# KelvinVoltageMeasureModule.net
KiCad netlist of a schematic drawn in Altium Designer
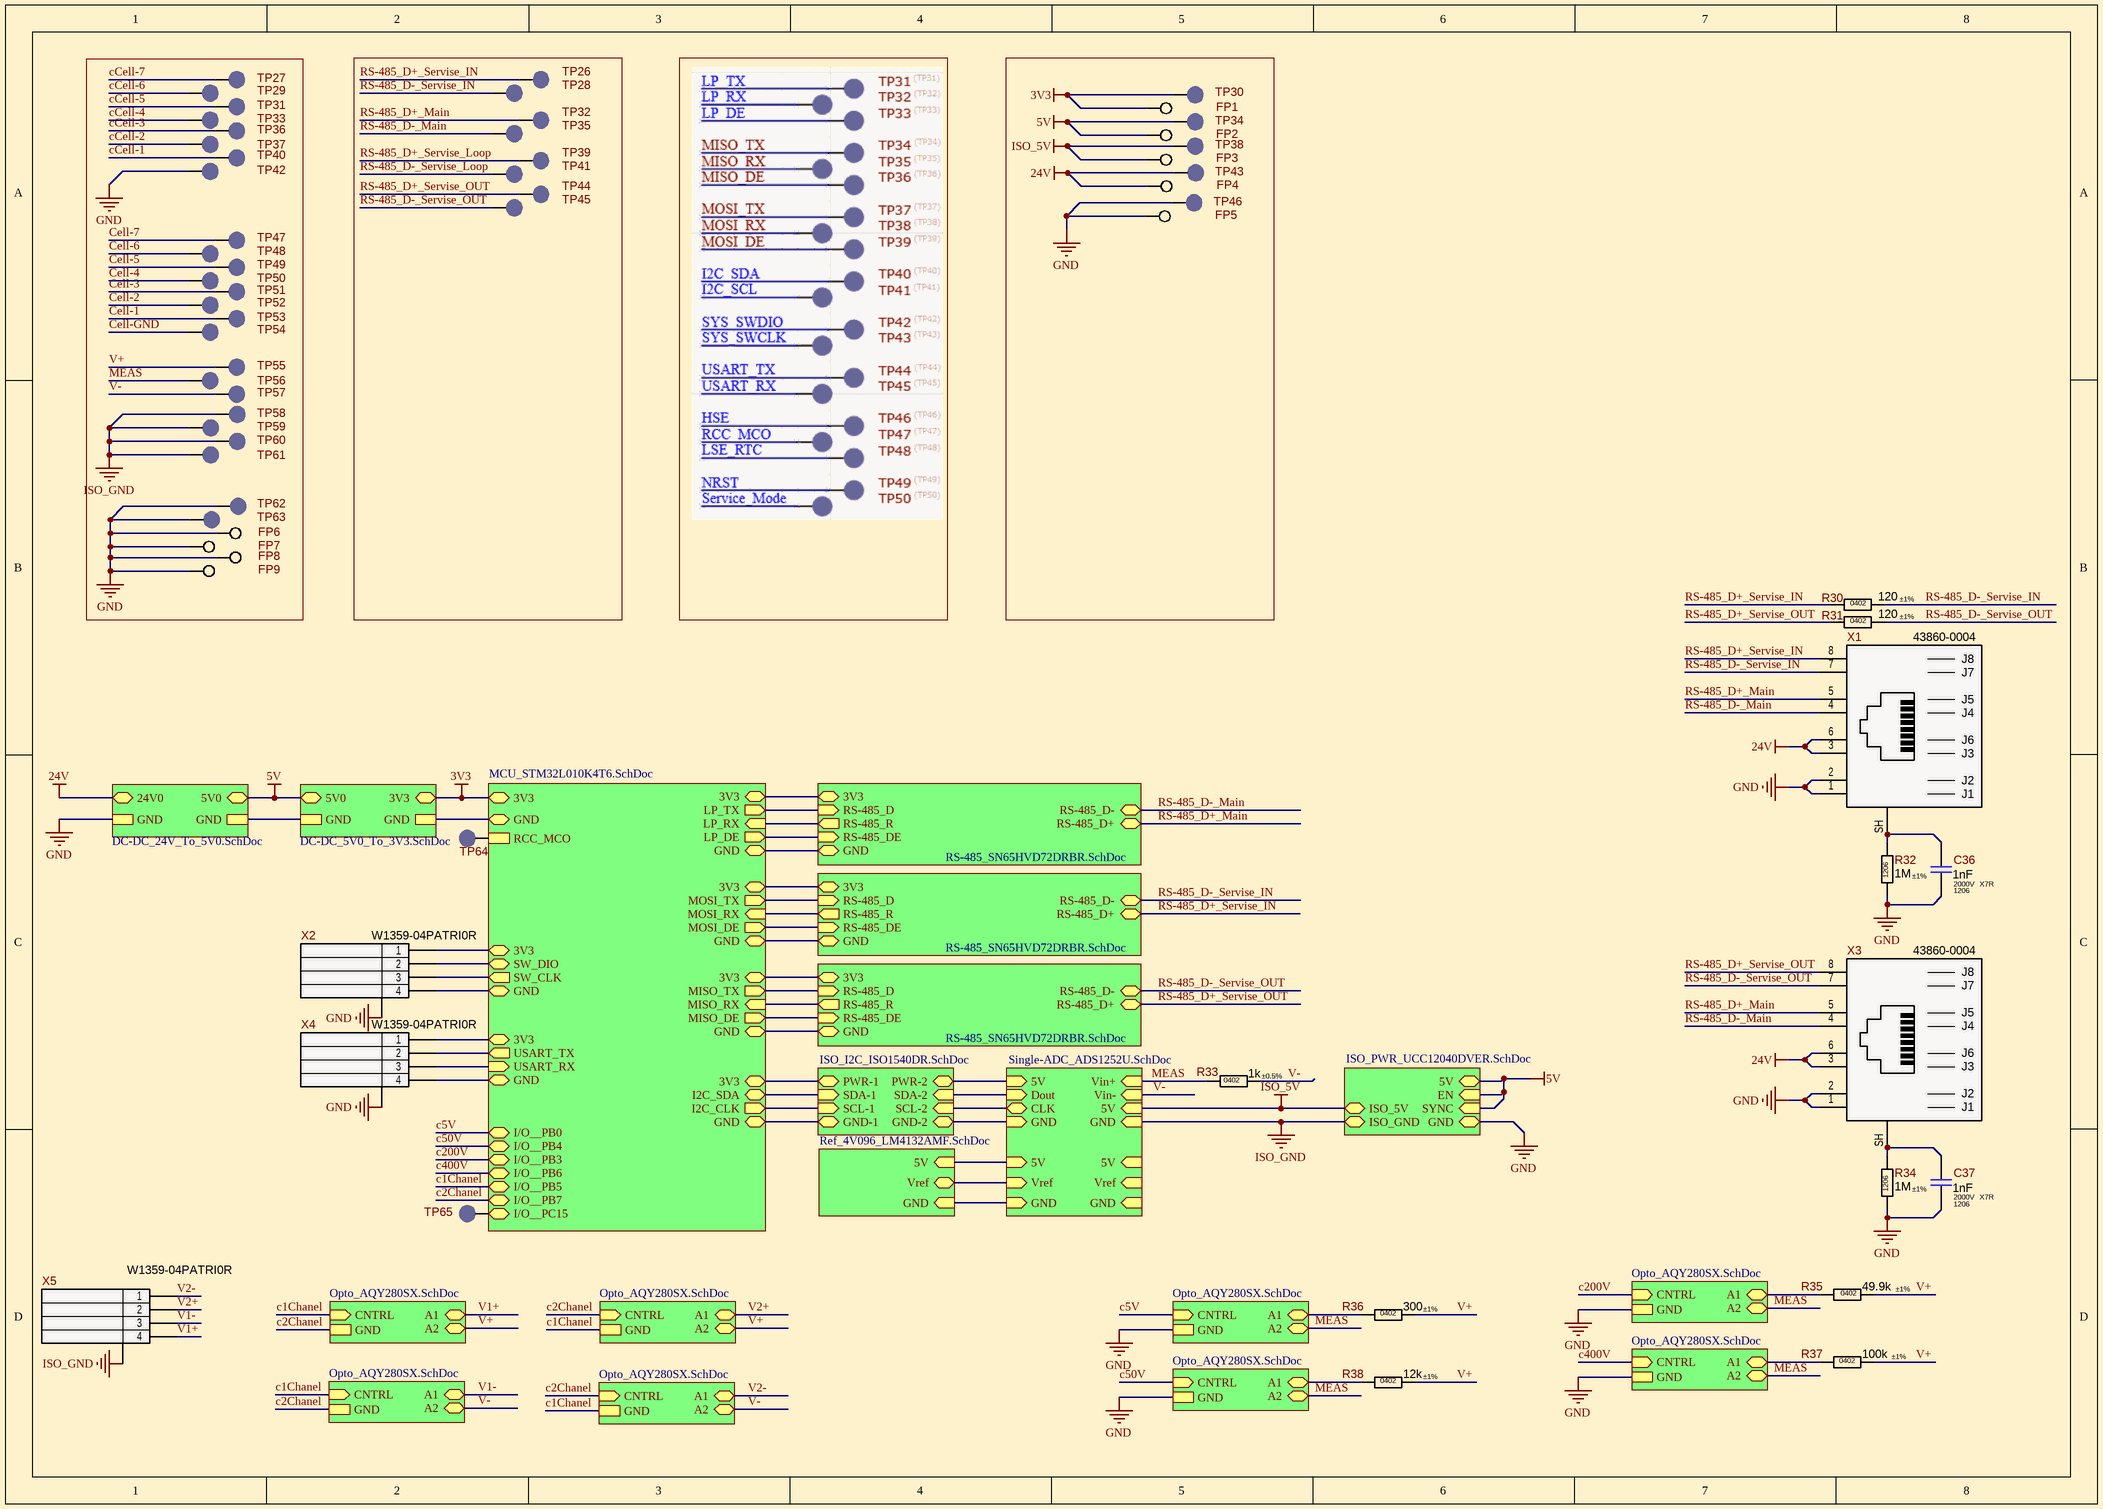
[diagram p0: KelvinVoltageMeasureModule.SchDoc]

(export (version "E")
  (design (tool "Eeschema 10.0.6"))
  (components
    (comp (ref "C36")
      (value "1nF")
      (footprint "CAP-1206(3216)X125T20")
      (description "1nF 2000V X7R ±10% 1206 Ceramic Capacitor RoHS")
      (fields
        (field (name "PACKAGE") "1206")
        (field (name "VOLTAGE") "2000V")
        (field (name "DIELECTRIC TYPE") "X7R")
        (field (name "PART NUMBER") "CC1206KKX7RDBB102")
        (field (name "MANUFACTURER") "Yageo")
      )
      (libsource (lib "EL.CVCM.T01") (part "Capacitor-NonPolar"))
    )
    (comp (ref "C37")
      (value "1nF")
      (footprint "CAP-1206(3216)X125T20")
      (description "1nF 2000V X7R ±10% 1206 Ceramic Capacitor RoHS")
      (fields
        (field (name "PACKAGE") "1206")
        (field (name "VOLTAGE") "2000V")
        (field (name "DIELECTRIC TYPE") "X7R")
        (field (name "PART NUMBER") "CC1206KKX7RDBB102")
        (field (name "MANUFACTURER") "Yageo")
      )
      (libsource (lib "EL.CVCM.T01") (part "Capacitor-NonPolar"))
    )
    (comp (ref "FP1")
      (value "PAD-1.1mm")
      (footprint "PAD-1.1mm")
      (description "1.1mm Pad for Plug-In or Receptacle")
      (fields (field (name "MANUFACTURER") "NONE"))
      (libsource (lib "EL.CVCM.T01") (part "Pad"))
    )
    (comp (ref "FP2")
      (value "PAD-1.1mm")
      (footprint "PAD-1.1mm")
      (description "1.1mm Pad for Plug-In or Receptacle")
      (fields (field (name "MANUFACTURER") "NONE"))
      (libsource (lib "EL.CVCM.T01") (part "Pad"))
    )
    (comp (ref "FP3")
      (value "PAD-1.1mm")
      (footprint "PAD-1.1mm")
      (description "1.1mm Pad for Plug-In or Receptacle")
      (fields (field (name "MANUFACTURER") "NONE"))
      (libsource (lib "EL.CVCM.T01") (part "Pad"))
    )
    (comp (ref "FP4")
      (value "PAD-1.1mm")
      (footprint "PAD-1.1mm")
      (description "1.1mm Pad for Plug-In or Receptacle")
      (fields (field (name "MANUFACTURER") "NONE"))
      (libsource (lib "EL.CVCM.T01") (part "Pad"))
    )
    (comp (ref "FP5")
      (value "PAD-1.1mm")
      (footprint "PAD-1.1mm")
      (description "1.1mm Pad for Plug-In or Receptacle")
      (fields (field (name "MANUFACTURER") "NONE"))
      (libsource (lib "EL.CVCM.T01") (part "Pad"))
    )
    (comp (ref "FP6")
      (value "PAD-1.1mm")
      (footprint "PAD-1.1mm")
      (description "1.1mm Pad for Plug-In or Receptacle")
      (fields (field (name "MANUFACTURER") "NONE"))
      (libsource (lib "EL.CVCM.T01") (part "Pad"))
    )
    (comp (ref "FP7")
      (value "PAD-1.1mm")
      (footprint "PAD-1.1mm")
      (description "1.1mm Pad for Plug-In or Receptacle")
      (fields (field (name "MANUFACTURER") "NONE"))
      (libsource (lib "EL.CVCM.T01") (part "Pad"))
    )
    (comp (ref "FP8")
      (value "PAD-1.1mm")
      (footprint "PAD-1.1mm")
      (description "1.1mm Pad for Plug-In or Receptacle")
      (fields (field (name "MANUFACTURER") "NONE"))
      (libsource (lib "EL.CVCM.T01") (part "Pad"))
    )
    (comp (ref "FP9")
      (value "PAD-1.1mm")
      (footprint "PAD-1.1mm")
      (description "1.1mm Pad for Plug-In or Receptacle")
      (fields (field (name "MANUFACTURER") "NONE"))
      (libsource (lib "EL.CVCM.T01") (part "Pad"))
    )
    (comp (ref "R30")
      (value "120")
      (footprint "R_ANY_CHIP_0402_HI")
      (description "120 Ohms ±1% 1/16W 0402 Thick Film Resistor")
      (fields
        (field (name "TOLERANCE") "±1%")
        (field (name "PACKAGE") "0402")
        (field (name "PART NUMBER") "RC0402FR-07120RL")
        (field (name "MANUFACTURER") "Yageo")
      )
      (libsource (lib "EL.CVCM.T01") (part "Resistor"))
    )
    (comp (ref "R31")
      (value "120")
      (footprint "R_ANY_CHIP_0402_HI")
      (description "120 Ohms ±1% 1/16W 0402 Thick Film Resistor")
      (fields
        (field (name "TOLERANCE") "±1%")
        (field (name "PACKAGE") "0402")
        (field (name "PART NUMBER") "RC0402FR-07120RL")
        (field (name "MANUFACTURER") "Yageo")
      )
      (libsource (lib "EL.CVCM.T01") (part "Resistor"))
    )
    (comp (ref "R32")
      (value "1M")
      (footprint "CHV1206-Series")
      (description "1 MOhms ±1%, 1/4W 1206 Thick Film Resistor")
      (fields
        (field (name "TOLERANCE") "±1%")
        (field (name "PACKAGE") "1206")
        (field (name "PART NUMBER") "CHV1206-FX-1004ELF")
        (field (name "MANUFACTURER") "Bourns")
      )
      (libsource (lib "EL.CVCM.T01") (part "Resistor"))
    )
    (comp (ref "R33")
      (value "1k")
      (footprint "R_ANY_CHIP_0402_MED")
      (description "1 kOhms ±0.5% 1/16W 0402 Thick Film Resistor")
      (fields
        (field (name "TOLERANCE") "±0.5%")
        (field (name "PACKAGE") "0402")
        (field (name "PART NUMBER") "RC0402DR-071KL")
        (field (name "MANUFACTURER") "Yageo")
      )
      (libsource (lib "EL.CVCM.T01") (part "Resistor"))
    )
    (comp (ref "R34")
      (value "1M")
      (footprint "CHV1206-Series")
      (description "1 MOhms ±1%, 1/4W 1206 Thick Film Resistor")
      (fields
        (field (name "TOLERANCE") "±1%")
        (field (name "PACKAGE") "1206")
        (field (name "PART NUMBER") "CHV1206-FX-1004ELF")
        (field (name "MANUFACTURER") "Bourns")
      )
      (libsource (lib "EL.CVCM.T01") (part "Resistor"))
    )
    (comp (ref "R35")
      (value "49.9k")
      (footprint "R_ANY_CHIP_0402_MED")
      (description "49.9 kOhms ±1% 1/16W 0402 Thick Film Resistor")
      (fields
        (field (name "PART NUMBER") "RC0402FR-0749K9L")
        (field (name "MANUFACTURER") "Yageo")
        (field (name "TOLERANCE") "±1%")
        (field (name "PACKAGE") "0402")
      )
      (libsource (lib "EL.XXX.T01") (part "RC0402FR-0749K9L"))
    )
    (comp (ref "R36")
      (value "300")
      (footprint "R_ANY_CHIP_0402_MED")
      (description "300 Ohms ±1% 1/16W 0402 Thick Film Resistor")
      (fields
        (field (name "PART NUMBER") "RC0402FR-07300RL")
        (field (name "MANUFACTURER") "Yageo")
        (field (name "TOLERANCE") "±1%")
        (field (name "PACKAGE") "0402")
      )
      (libsource (lib "EL.XXX.T01") (part "RC0402FR-07300RL"))
    )
    (comp (ref "R37")
      (value "100k")
      (footprint "R_ANY_CHIP_0402_MED")
      (description "100 kOhms ±1% 1/16W 0402 Thick Film Resistor")
      (fields
        (field (name "PART NUMBER") "RC0402FR-07100KL")
        (field (name "MANUFACTURER") "Yageo")
        (field (name "TOLERANCE") "±1%")
        (field (name "PACKAGE") "0402")
      )
      (libsource (lib "EL.XXX.T01") (part "RC0402FR-07100KL"))
    )
    (comp (ref "R38")
      (value "12k")
      (footprint "R_ANY_CHIP_0402_MED")
      (description "12 kOhms ±1% 1/16W 0402 Thick Film Resistor")
      (fields
        (field (name "PART NUMBER") "RC0402FR-0712KL")
        (field (name "MANUFACTURER") "Yageo")
        (field (name "TOLERANCE") "±1%")
        (field (name "PACKAGE") "0402")
      )
      (libsource (lib "EL.XXX.T01") (part "RC0402FR-0712KL"))
    )
    (comp (ref "TP26")
      (value "LED_LINK")
      (footprint "TP_SMD_2mm")
      (description "Test Point SMD Pad 1.0mm/1.5mm/2mm")
      (fields (field (name "PART NUMBER") "TP-PAD-SMD"))
      (libsource (lib "EL.CVCM.T01") (part "Test-Point-SMD-1"))
    )
    (comp (ref "TP27")
      (value "LED_LINK")
      (footprint "TP_SMD_2mm")
      (description "Test Point SMD Pad 1.0mm/1.5mm/2mm")
      (fields (field (name "PART NUMBER") "TP-PAD-SMD"))
      (libsource (lib "EL.CVCM.T01") (part "Test-Point-SMD-1"))
    )
    (comp (ref "TP28")
      (value "LED_LINK")
      (footprint "TP_SMD_2mm")
      (description "Test Point SMD Pad 1.0mm/1.5mm/2mm")
      (fields (field (name "PART NUMBER") "TP-PAD-SMD"))
      (libsource (lib "EL.CVCM.T01") (part "Test-Point-SMD-1"))
    )
    (comp (ref "TP29")
      (value "LED_LINK")
      (footprint "TP_SMD_2mm")
      (description "Test Point SMD Pad 1.0mm/1.5mm/2mm")
      (fields (field (name "PART NUMBER") "TP-PAD-SMD"))
      (libsource (lib "EL.CVCM.T01") (part "Test-Point-SMD-1"))
    )
    (comp (ref "TP30")
      (value "LED_LINK")
      (footprint "TP_SMD_2mm")
      (description "Test Point SMD Pad 1.0mm/1.5mm/2mm")
      (fields (field (name "PART NUMBER") "TP-PAD-SMD"))
      (libsource (lib "EL.CVCM.T01") (part "Test-Point-SMD-1"))
    )
    (comp (ref "TP31")
      (value "LED_LINK")
      (footprint "TP_SMD_2mm")
      (description "Test Point SMD Pad 1.0mm/1.5mm/2mm")
      (fields (field (name "PART NUMBER") "TP-PAD-SMD"))
      (libsource (lib "EL.CVCM.T01") (part "Test-Point-SMD-1"))
    )
    (comp (ref "TP32")
      (value "LED_LINK")
      (footprint "TP_SMD_2mm")
      (description "Test Point SMD Pad 1.0mm/1.5mm/2mm")
      (fields (field (name "PART NUMBER") "TP-PAD-SMD"))
      (libsource (lib "EL.CVCM.T01") (part "Test-Point-SMD-1"))
    )
    (comp (ref "TP33")
      (value "LED_LINK")
      (footprint "TP_SMD_2mm")
      (description "Test Point SMD Pad 1.0mm/1.5mm/2mm")
      (fields (field (name "PART NUMBER") "TP-PAD-SMD"))
      (libsource (lib "EL.CVCM.T01") (part "Test-Point-SMD-1"))
    )
    (comp (ref "TP34")
      (value "LED_LINK")
      (footprint "TP_SMD_2mm")
      (description "Test Point SMD Pad 1.0mm/1.5mm/2mm")
      (fields (field (name "PART NUMBER") "TP-PAD-SMD"))
      (libsource (lib "EL.CVCM.T01") (part "Test-Point-SMD-1"))
    )
    (comp (ref "TP35")
      (value "LED_LINK")
      (footprint "TP_SMD_2mm")
      (description "Test Point SMD Pad 1.0mm/1.5mm/2mm")
      (fields (field (name "PART NUMBER") "TP-PAD-SMD"))
      (libsource (lib "EL.CVCM.T01") (part "Test-Point-SMD-1"))
    )
    (comp (ref "TP36")
      (value "LED_LINK")
      (footprint "TP_SMD_2mm")
      (description "Test Point SMD Pad 1.0mm/1.5mm/2mm")
      (fields (field (name "PART NUMBER") "TP-PAD-SMD"))
      (libsource (lib "EL.CVCM.T01") (part "Test-Point-SMD-1"))
    )
    (comp (ref "TP37")
      (value "LED_LINK")
      (footprint "TP_SMD_2mm")
      (description "Test Point SMD Pad 1.0mm/1.5mm/2mm")
      (fields (field (name "PART NUMBER") "TP-PAD-SMD"))
      (libsource (lib "EL.CVCM.T01") (part "Test-Point-SMD-1"))
    )
    (comp (ref "TP38")
      (value "LED_LINK")
      (footprint "TP_SMD_2mm")
      (description "Test Point SMD Pad 1.0mm/1.5mm/2mm")
      (fields (field (name "PART NUMBER") "TP-PAD-SMD"))
      (libsource (lib "EL.CVCM.T01") (part "Test-Point-SMD-1"))
    )
    (comp (ref "TP39")
      (value "LED_LINK")
      (footprint "TP_SMD_2mm")
      (description "Test Point SMD Pad 1.0mm/1.5mm/2mm")
      (fields (field (name "PART NUMBER") "TP-PAD-SMD"))
      (libsource (lib "EL.CVCM.T01") (part "Test-Point-SMD-1"))
    )
    (comp (ref "TP40")
      (value "LED_LINK")
      (footprint "TP_SMD_2mm")
      (description "Test Point SMD Pad 1.0mm/1.5mm/2mm")
      (fields (field (name "PART NUMBER") "TP-PAD-SMD"))
      (libsource (lib "EL.CVCM.T01") (part "Test-Point-SMD-1"))
    )
    (comp (ref "TP41")
      (value "LED_LINK")
      (footprint "TP_SMD_2mm")
      (description "Test Point SMD Pad 1.0mm/1.5mm/2mm")
      (fields (field (name "PART NUMBER") "TP-PAD-SMD"))
      (libsource (lib "EL.CVCM.T01") (part "Test-Point-SMD-1"))
    )
    (comp (ref "TP42")
      (value "LED_LINK")
      (footprint "TP_SMD_2mm")
      (description "Test Point SMD Pad 1.0mm/1.5mm/2mm")
      (fields (field (name "PART NUMBER") "TP-PAD-SMD"))
      (libsource (lib "EL.CVCM.T01") (part "Test-Point-SMD-1"))
    )
    (comp (ref "TP43")
      (value "LED_LINK")
      (footprint "TP_SMD_2mm")
      (description "Test Point SMD Pad 1.0mm/1.5mm/2mm")
      (fields (field (name "PART NUMBER") "TP-PAD-SMD"))
      (libsource (lib "EL.CVCM.T01") (part "Test-Point-SMD-1"))
    )
    (comp (ref "TP44")
      (value "LED_LINK")
      (footprint "TP_SMD_2mm")
      (description "Test Point SMD Pad 1.0mm/1.5mm/2mm")
      (fields (field (name "PART NUMBER") "TP-PAD-SMD"))
      (libsource (lib "EL.CVCM.T01") (part "Test-Point-SMD-1"))
    )
    (comp (ref "TP45")
      (value "LED_LINK")
      (footprint "TP_SMD_2mm")
      (description "Test Point SMD Pad 1.0mm/1.5mm/2mm")
      (fields (field (name "PART NUMBER") "TP-PAD-SMD"))
      (libsource (lib "EL.CVCM.T01") (part "Test-Point-SMD-1"))
    )
    (comp (ref "TP46")
      (value "LED_LINK")
      (footprint "TP_SMD_2mm")
      (description "Test Point SMD Pad 1.0mm/1.5mm/2mm")
      (fields (field (name "PART NUMBER") "TP-PAD-SMD"))
      (libsource (lib "EL.CVCM.T01") (part "Test-Point-SMD-1"))
    )
    (comp (ref "TP47")
      (value "LED_LINK")
      (footprint "TP_SMD_2mm")
      (description "Test Point SMD Pad 1.0mm/1.5mm/2mm")
      (fields (field (name "PART NUMBER") "TP-PAD-SMD"))
      (libsource (lib "EL.CVCM.T01") (part "Test-Point-SMD-1"))
    )
    (comp (ref "TP48")
      (value "LED_LINK")
      (footprint "TP_SMD_2mm")
      (description "Test Point SMD Pad 1.0mm/1.5mm/2mm")
      (fields (field (name "PART NUMBER") "TP-PAD-SMD"))
      (libsource (lib "EL.CVCM.T01") (part "Test-Point-SMD-1"))
    )
    (comp (ref "TP49")
      (value "LED_LINK")
      (footprint "TP_SMD_2mm")
      (description "Test Point SMD Pad 1.0mm/1.5mm/2mm")
      (fields (field (name "PART NUMBER") "TP-PAD-SMD"))
      (libsource (lib "EL.CVCM.T01") (part "Test-Point-SMD-1"))
    )
    (comp (ref "TP50")
      (value "LED_LINK")
      (footprint "TP_SMD_2mm")
      (description "Test Point SMD Pad 1.0mm/1.5mm/2mm")
      (fields (field (name "PART NUMBER") "TP-PAD-SMD"))
      (libsource (lib "EL.CVCM.T01") (part "Test-Point-SMD-1"))
    )
    (comp (ref "TP51")
      (value "LED_LINK")
      (footprint "TP_SMD_2mm")
      (description "Test Point SMD Pad 1.0mm/1.5mm/2mm")
      (fields (field (name "PART NUMBER") "TP-PAD-SMD"))
      (libsource (lib "EL.CVCM.T01") (part "Test-Point-SMD-1"))
    )
    (comp (ref "TP52")
      (value "LED_LINK")
      (footprint "TP_SMD_2mm")
      (description "Test Point SMD Pad 1.0mm/1.5mm/2mm")
      (fields (field (name "PART NUMBER") "TP-PAD-SMD"))
      (libsource (lib "EL.CVCM.T01") (part "Test-Point-SMD-1"))
    )
    (comp (ref "TP53")
      (value "LED_LINK")
      (footprint "TP_SMD_2mm")
      (description "Test Point SMD Pad 1.0mm/1.5mm/2mm")
      (fields (field (name "PART NUMBER") "TP-PAD-SMD"))
      (libsource (lib "EL.CVCM.T01") (part "Test-Point-SMD-1"))
    )
    (comp (ref "TP54")
      (value "LED_LINK")
      (footprint "TP_SMD_2mm")
      (description "Test Point SMD Pad 1.0mm/1.5mm/2mm")
      (fields (field (name "PART NUMBER") "TP-PAD-SMD"))
      (libsource (lib "EL.CVCM.T01") (part "Test-Point-SMD-1"))
    )
    (comp (ref "TP55")
      (value "LED_LINK")
      (footprint "TP_SMD_2mm")
      (description "Test Point SMD Pad 1.0mm/1.5mm/2mm")
      (fields (field (name "PART NUMBER") "TP-PAD-SMD"))
      (libsource (lib "EL.CVCM.T01") (part "Test-Point-SMD-1"))
    )
    (comp (ref "TP56")
      (value "LED_LINK")
      (footprint "TP_SMD_2mm")
      (description "Test Point SMD Pad 1.0mm/1.5mm/2mm")
      (fields (field (name "PART NUMBER") "TP-PAD-SMD"))
      (libsource (lib "EL.CVCM.T01") (part "Test-Point-SMD-1"))
    )
    (comp (ref "TP57")
      (value "LED_LINK")
      (footprint "TP_SMD_2mm")
      (description "Test Point SMD Pad 1.0mm/1.5mm/2mm")
      (fields (field (name "PART NUMBER") "TP-PAD-SMD"))
      (libsource (lib "EL.CVCM.T01") (part "Test-Point-SMD-1"))
    )
    (comp (ref "TP58")
      (value "LED_LINK")
      (footprint "TP_SMD_2mm")
      (description "Test Point SMD Pad 1.0mm/1.5mm/2mm")
      (fields (field (name "PART NUMBER") "TP-PAD-SMD"))
      (libsource (lib "EL.CVCM.T01") (part "Test-Point-SMD-1"))
    )
    (comp (ref "TP59")
      (value "LED_LINK")
      (footprint "TP_SMD_2mm")
      (description "Test Point SMD Pad 1.0mm/1.5mm/2mm")
      (fields (field (name "PART NUMBER") "TP-PAD-SMD"))
      (libsource (lib "EL.CVCM.T01") (part "Test-Point-SMD-1"))
    )
    (comp (ref "TP60")
      (value "LED_LINK")
      (footprint "TP_SMD_2mm")
      (description "Test Point SMD Pad 1.0mm/1.5mm/2mm")
      (fields (field (name "PART NUMBER") "TP-PAD-SMD"))
      (libsource (lib "EL.CVCM.T01") (part "Test-Point-SMD-1"))
    )
    (comp (ref "TP61")
      (value "LED_LINK")
      (footprint "TP_SMD_2mm")
      (description "Test Point SMD Pad 1.0mm/1.5mm/2mm")
      (fields (field (name "PART NUMBER") "TP-PAD-SMD"))
      (libsource (lib "EL.CVCM.T01") (part "Test-Point-SMD-1"))
    )
    (comp (ref "TP62")
      (value "LED_LINK")
      (footprint "TP_SMD_2mm")
      (description "Test Point SMD Pad 1.0mm/1.5mm/2mm")
      (fields (field (name "PART NUMBER") "TP-PAD-SMD"))
      (libsource (lib "EL.CVCM.T01") (part "Test-Point-SMD-1"))
    )
    (comp (ref "TP63")
      (value "LED_LINK")
      (footprint "TP_SMD_2mm")
      (description "Test Point SMD Pad 1.0mm/1.5mm/2mm")
      (fields (field (name "PART NUMBER") "TP-PAD-SMD"))
      (libsource (lib "EL.CVCM.T01") (part "Test-Point-SMD-1"))
    )
    (comp (ref "TP64")
      (value "LED_LINK")
      (footprint "TP_SMD_2mm")
      (description "Test Point SMD Pad 1.0mm/1.5mm/2mm")
      (fields (field (name "PART NUMBER") "TP-PAD-SMD"))
      (libsource (lib "EL.CVCM.T01") (part "Test-Point-SMD-1"))
    )
    (comp (ref "TP65")
      (value "LED_LINK")
      (footprint "TP_SMD_2mm")
      (description "Test Point SMD Pad 1.0mm/1.5mm/2mm")
      (fields (field (name "PART NUMBER") "TP-PAD-SMD"))
      (libsource (lib "EL.CVCM.T01") (part "Test-Point-SMD-1"))
    )
    (comp (ref "X1")
      (value "43860-0004")
      (footprint "43860-0004")
      (description "RJ45 8P8C Shielded Cat 3 10 Base-T Connector")
      (fields (field (name "PART NUMBER") "43860-0004") (field (name "MANUFACTURER") "Molex"))
      (libsource (lib "EL.CVCM.T01") (part "43860-0004"))
    )
    (comp (ref "X2")
      (value "W1359-04PATRI0R")
      (footprint "W1359-04PATXI0R_DBG")
      (description "1.25mm Wire-to-Board Header, Vertical, SMT, 4 pin")
      (fields
        (field (name "PART NUMBER") "W1359-04PATRI0R")
        (field (name "MANUFACTURER") "Hsuan Mao Technology")
      )
      (libsource (lib "EL.CVCM.T01") (part "General-4-Pin-MP"))
    )
    (comp (ref "X3")
      (value "43860-0004")
      (footprint "43860-0004")
      (description "RJ45 8P8C Shielded Cat 3 10 Base-T Connector")
      (fields (field (name "PART NUMBER") "43860-0004") (field (name "MANUFACTURER") "Molex"))
      (libsource (lib "EL.CVCM.T01") (part "43860-0004"))
    )
    (comp (ref "X4")
      (value "W1359-04PATRI0R")
      (footprint "W1359-04PATXI0R_DBG")
      (description "1.25mm Wire-to-Board Header, Vertical, SMT, 4 pin")
      (fields
        (field (name "PART NUMBER") "W1359-04PATRI0R")
        (field (name "MANUFACTURER") "Hsuan Mao Technology")
      )
      (libsource (lib "EL.CVCM.T01") (part "General-4-Pin-MP"))
    )
    (comp (ref "X5")
      (value "W1359-04PATRI0R")
      (footprint "W1359-04PATXI0R_DBG")
      (description "1.25mm Wire-to-Board Header, Vertical, SMT, 4 pin")
      (fields
        (field (name "PART NUMBER") "W1359-04PATRI0R")
        (field (name "MANUFACTURER") "Hsuan Mao Technology")
      )
      (libsource (lib "EL.CVCM.T01") (part "General-4-Pin-MP"))
    )
  )
  (nets
    (net (code "2") (name "/3V3_1") (class "Default")
      (node (ref "X4") (pin "1") (pinfunction "1_1") (pintype "passive"))
    )
    (net (code "3") (name "/3V3_2") (class "Default")
      (node (ref "X2") (pin "1") (pinfunction "1_1") (pintype "passive"))
    )
    (net (code "13") (name "/A1") (class "Default") (node (ref "R37") (pin "2") (pintype "passive")))
    (net (code "14") (name "/A1_1") (class "Default") (node (ref "R36") (pin "2") (pintype "passive")))
    (net (code "15") (name "/A1_2") (class "Default") (node (ref "R38") (pin "2") (pintype "passive")))
    (net (code "16") (name "/A1_3") (class "Default") (node (ref "R35") (pin "2") (pintype "passive")))
    (net (code "18") (name "/Cell-1") (class "Default") (node (ref "TP53") (pin "1") (pintype "passive")))
    (net (code "19") (name "/Cell-2") (class "Default") (node (ref "TP52") (pin "1") (pintype "passive")))
    (net (code "20") (name "/Cell-3") (class "Default") (node (ref "TP51") (pin "1") (pintype "passive")))
    (net (code "21") (name "/Cell-4") (class "Default") (node (ref "TP50") (pin "1") (pintype "passive")))
    (net (code "22") (name "/Cell-5") (class "Default") (node (ref "TP49") (pin "1") (pintype "passive")))
    (net (code "23") (name "/Cell-6") (class "Default") (node (ref "TP48") (pin "1") (pintype "passive")))
    (net (code "24") (name "/Cell-7") (class "Default") (node (ref "TP47") (pin "1") (pintype "passive")))
    (net (code "25") (name "/Cell-GND") (class "Default") (node (ref "TP54") (pin "1") (pintype "passive")))
    (net (code "28") (name "/GND_1") (class "Default")
      (node (ref "X4") (pin "4") (pinfunction "4_4") (pintype "passive"))
    )
    (net (code "29") (name "/GND_2") (class "Default")
      (node (ref "X2") (pin "4") (pinfunction "4_4") (pintype "passive"))
    )
    (net (code "43") (name "/I{slash}O__PC15") (class "Default")
      (node (ref "TP65") (pin "1") (pintype "passive"))
    )
    (net (code "47") (name "/MEAS") (class "Default")
      (node (ref "R33") (pin "1") (pintype "passive"))
      (node (ref "TP56") (pin "1") (pintype "passive"))
    )
    (net (code "54") (name "/RCC_MCO") (class "Default") (node (ref "TP64") (pin "1") (pintype "passive")))
    (net (code "56") (name "/RS-485_D+_Main") (class "Default")
      (node (ref "TP32") (pin "1") (pintype "passive"))
      (node (ref "X1") (pin "5") (pinfunction "CT_5") (pintype "passive"))
      (node (ref "X3") (pin "5") (pinfunction "CT_5") (pintype "passive"))
    )
    (net (code "57") (name "/RS-485_D+_Servise_IN") (class "Default")
      (node (ref "R30") (pin "1") (pintype "passive"))
      (node (ref "TP26") (pin "1") (pintype "passive"))
      (node (ref "X1") (pin "8") (pinfunction "TD2+_8") (pintype "passive"))
    )
    (net (code "58") (name "/RS-485_D+_Servise_Loop") (class "Default")
      (node (ref "TP39") (pin "1") (pintype "passive"))
    )
    (net (code "59") (name "/RS-485_D+_Servise_OUT") (class "Default")
      (node (ref "R31") (pin "1") (pintype "passive"))
      (node (ref "TP44") (pin "1") (pintype "passive"))
      (node (ref "X3") (pin "8") (pinfunction "TD2+_8") (pintype "passive"))
    )
    (net (code "60") (name "/RS-485_D-_Main") (class "Default")
      (node (ref "TP35") (pin "1") (pintype "passive"))
      (node (ref "X1") (pin "4") (pinfunction "TD3+_4") (pintype "passive"))
      (node (ref "X3") (pin "4") (pinfunction "TD3+_4") (pintype "passive"))
    )
    (net (code "61") (name "/RS-485_D-_Servise_IN") (class "Default")
      (node (ref "R30") (pin "2") (pintype "passive"))
      (node (ref "TP28") (pin "1") (pintype "passive"))
      (node (ref "X1") (pin "7") (pinfunction "TD2-_7") (pintype "passive"))
    )
    (net (code "62") (name "/RS-485_D-_Servise_Loop") (class "Default")
      (node (ref "TP41") (pin "1") (pintype "passive"))
    )
    (net (code "63") (name "/RS-485_D-_Servise_OUT") (class "Default")
      (node (ref "R31") (pin "2") (pintype "passive"))
      (node (ref "TP45") (pin "1") (pintype "passive"))
      (node (ref "X3") (pin "7") (pinfunction "TD2-_7") (pintype "passive"))
    )
    (net (code "72") (name "/SW_CLK") (class "Default")
      (node (ref "X2") (pin "3") (pinfunction "3_3") (pintype "passive"))
    )
    (net (code "73") (name "/SW_DIO") (class "Default")
      (node (ref "X2") (pin "2") (pinfunction "2_2") (pintype "passive"))
    )
    (net (code "74") (name "/USART_RX") (class "Default")
      (node (ref "X4") (pin "3") (pinfunction "3_3") (pintype "passive"))
    )
    (net (code "75") (name "/USART_TX") (class "Default")
      (node (ref "X4") (pin "2") (pinfunction "2_2") (pintype "passive"))
    )
    (net (code "76") (name "/V+") (class "Default")
      (node (ref "R35") (pin "1") (pintype "passive"))
      (node (ref "R36") (pin "1") (pintype "passive"))
      (node (ref "R37") (pin "1") (pintype "passive"))
      (node (ref "R38") (pin "1") (pintype "passive"))
      (node (ref "TP55") (pin "1") (pintype "passive"))
    )
    (net (code "77") (name "/V-") (class "Default")
      (node (ref "R33") (pin "2") (pintype "passive"))
      (node (ref "TP57") (pin "1") (pintype "passive"))
    )
    (net (code "78") (name "/V1+") (class "Default")
      (node (ref "X5") (pin "4") (pinfunction "4_4") (pintype "passive"))
    )
    (net (code "79") (name "/V1-") (class "Default")
      (node (ref "X5") (pin "3") (pinfunction "3_3") (pintype "passive"))
    )
    (net (code "80") (name "/V2+") (class "Default")
      (node (ref "X5") (pin "2") (pinfunction "2_2") (pintype "passive"))
    )
    (net (code "81") (name "/V2-") (class "Default")
      (node (ref "X5") (pin "1") (pinfunction "1_1") (pintype "passive"))
    )
    (net (code "90") (name "/cCell-1") (class "Default") (node (ref "TP40") (pin "1") (pintype "passive")))
    (net (code "91") (name "/cCell-2") (class "Default") (node (ref "TP37") (pin "1") (pintype "passive")))
    (net (code "92") (name "/cCell-3") (class "Default") (node (ref "TP36") (pin "1") (pintype "passive")))
    (net (code "93") (name "/cCell-4") (class "Default") (node (ref "TP33") (pin "1") (pintype "passive")))
    (net (code "94") (name "/cCell-5") (class "Default") (node (ref "TP31") (pin "1") (pintype "passive")))
    (net (code "95") (name "/cCell-6") (class "Default") (node (ref "TP29") (pin "1") (pintype "passive")))
    (net (code "96") (name "/cCell-7") (class "Default") (node (ref "TP27") (pin "1") (pintype "passive")))
    (net (code "97") (name "3V3") (class "Default")
      (node (ref "FP1") (pin "1") (pintype "passive"))
      (node (ref "TP30") (pin "1") (pintype "passive"))
    )
    (net (code "98") (name "5V") (class "Default")
      (node (ref "FP2") (pin "1") (pintype "passive"))
      (node (ref "TP34") (pin "1") (pintype "passive"))
    )
    (net (code "99") (name "24V") (class "Default")
      (node (ref "FP4") (pin "1") (pintype "passive"))
      (node (ref "TP43") (pin "1") (pintype "passive"))
      (node (ref "X1") (pin "3") (pinfunction "TD3-_3") (pintype "passive"))
      (node (ref "X1") (pin "6") (pinfunction "CT_6") (pintype "passive"))
      (node (ref "X3") (pin "3") (pinfunction "TD3-_3") (pintype "passive"))
      (node (ref "X3") (pin "6") (pinfunction "CT_6") (pintype "passive"))
    )
    (net (code "100") (name "GND") (class "Default")
      (node (ref "C36") (pin "2") (pinfunction "2_2") (pintype "passive"))
      (node (ref "C37") (pin "2") (pinfunction "2_2") (pintype "passive"))
      (node (ref "FP5") (pin "1") (pintype "passive"))
      (node (ref "FP6") (pin "1") (pintype "passive"))
      (node (ref "FP7") (pin "1") (pintype "passive"))
      (node (ref "FP8") (pin "1") (pintype "passive"))
      (node (ref "FP9") (pin "1") (pintype "passive"))
      (node (ref "R32") (pin "2") (pintype "passive"))
      (node (ref "R34") (pin "2") (pintype "passive"))
      (node (ref "TP42") (pin "1") (pintype "passive"))
      (node (ref "TP46") (pin "1") (pintype "passive"))
      (node (ref "TP62") (pin "1") (pintype "passive"))
      (node (ref "TP63") (pin "1") (pintype "passive"))
      (node (ref "X1") (pin "1") (pinfunction "TD4-_1") (pintype "passive"))
      (node (ref "X1") (pin "2") (pinfunction "TD4+_2") (pintype "passive"))
      (node (ref "X2") (pin "MP") (pinfunction "MountPad_MP") (pintype "passive"))
      (node (ref "X3") (pin "1") (pinfunction "TD4-_1") (pintype "passive"))
      (node (ref "X3") (pin "2") (pinfunction "TD4+_2") (pintype "passive"))
      (node (ref "X4") (pin "MP") (pinfunction "MountPad_MP") (pintype "passive"))
    )
    (net (code "101") (name "ISO_5V") (class "Default")
      (node (ref "FP3") (pin "1") (pintype "passive"))
      (node (ref "TP38") (pin "1") (pintype "passive"))
    )
    (net (code "102") (name "ISO_GND") (class "Default")
      (node (ref "TP58") (pin "1") (pintype "passive"))
      (node (ref "TP59") (pin "1") (pintype "passive"))
      (node (ref "TP60") (pin "1") (pintype "passive"))
      (node (ref "TP61") (pin "1") (pintype "passive"))
      (node (ref "X5") (pin "MP") (pinfunction "MountPad_MP") (pintype "passive"))
    )
    (net (code "103") (name "Net-(X1-Shield)") (class "Default")
      (node (ref "C36") (pin "1") (pinfunction "1_1") (pintype "passive"))
      (node (ref "R32") (pin "1") (pintype "passive"))
      (node (ref "X1") (pin "SH") (pinfunction "Shield_SH") (pintype "passive"))
    )
    (net (code "104") (name "Net-(X3-Shield)") (class "Default")
      (node (ref "C37") (pin "1") (pinfunction "1_1") (pintype "passive"))
      (node (ref "R34") (pin "1") (pintype "passive"))
      (node (ref "X3") (pin "SH") (pinfunction "Shield_SH") (pintype "passive"))
    )
  )
)
